# board.net
KiCad netlist of a schematic drawn in EAGLE
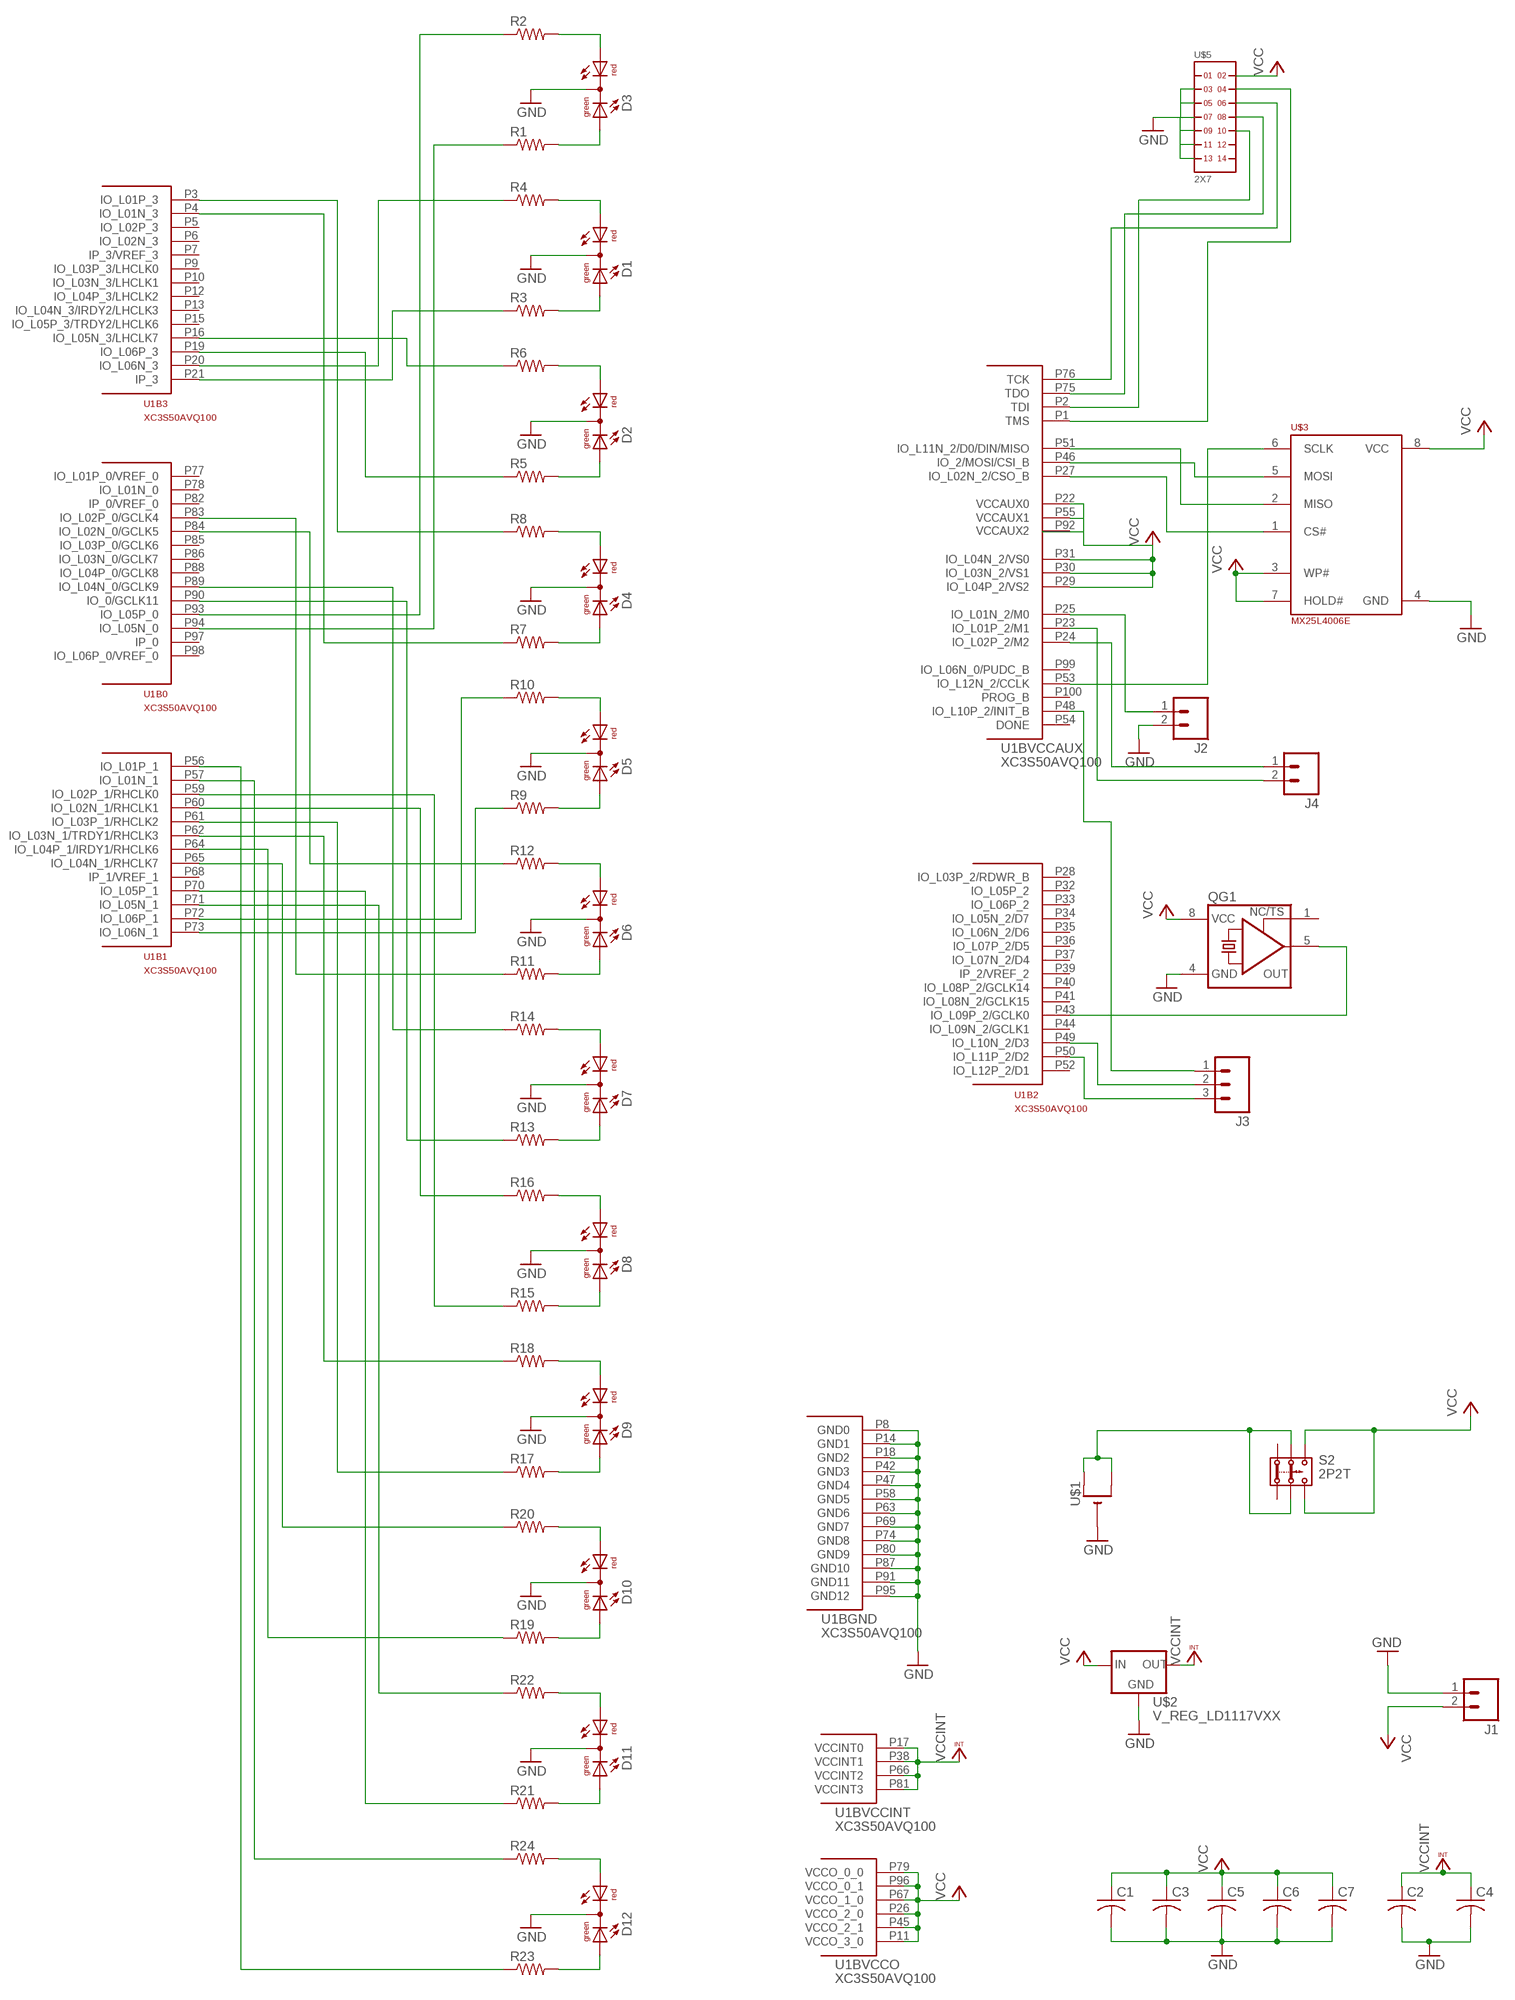
[diagram p0: schematic, sheet 1]

(export (version "E")
  (design (tool "Eeschema 10.0.6"))
  (components
    (comp (ref "C1")
      (value "C-USC0805")
      (footprint "eagle-import:C0805")
      (libsource (lib "eagle-import") (part "C-USC0805"))
    )
    (comp (ref "C2")
      (value "C-USC0805")
      (footprint "eagle-import:C0805")
      (libsource (lib "eagle-import") (part "C-USC0805"))
    )
    (comp (ref "C3")
      (value "C-USC0805")
      (footprint "eagle-import:C0805")
      (libsource (lib "eagle-import") (part "C-USC0805"))
    )
    (comp (ref "C4")
      (value "C-USC0805")
      (footprint "eagle-import:C0805")
      (libsource (lib "eagle-import") (part "C-USC0805"))
    )
    (comp (ref "C5")
      (value "C-USC0805")
      (footprint "eagle-import:C0805")
      (libsource (lib "eagle-import") (part "C-USC0805"))
    )
    (comp (ref "C6")
      (value "C-USC0805")
      (footprint "eagle-import:C0805")
      (libsource (lib "eagle-import") (part "C-USC0805"))
    )
    (comp (ref "C7")
      (value "C-USC0805")
      (footprint "eagle-import:C0805")
      (libsource (lib "eagle-import") (part "C-USC0805"))
    )
    (comp (ref "D1")
      (value "DUOLED5MM")
      (footprint "eagle-import:DUOLED5MM")
      (libsource (lib "eagle-import") (part "DUOLED5MM"))
    )
    (comp (ref "D2")
      (value "DUOLED5MM")
      (footprint "eagle-import:DUOLED5MM")
      (libsource (lib "eagle-import") (part "DUOLED5MM"))
    )
    (comp (ref "D3")
      (value "DUOLED5MM")
      (footprint "eagle-import:DUOLED5MM")
      (libsource (lib "eagle-import") (part "DUOLED5MM"))
    )
    (comp (ref "D4")
      (value "DUOLED5MM")
      (footprint "eagle-import:DUOLED5MM")
      (libsource (lib "eagle-import") (part "DUOLED5MM"))
    )
    (comp (ref "D5")
      (value "DUOLED5MM")
      (footprint "eagle-import:DUOLED5MM")
      (libsource (lib "eagle-import") (part "DUOLED5MM"))
    )
    (comp (ref "D6")
      (value "DUOLED5MM")
      (footprint "eagle-import:DUOLED5MM")
      (libsource (lib "eagle-import") (part "DUOLED5MM"))
    )
    (comp (ref "D7")
      (value "DUOLED5MM")
      (footprint "eagle-import:DUOLED5MM")
      (libsource (lib "eagle-import") (part "DUOLED5MM"))
    )
    (comp (ref "D8")
      (value "DUOLED5MM")
      (footprint "eagle-import:DUOLED5MM")
      (libsource (lib "eagle-import") (part "DUOLED5MM"))
    )
    (comp (ref "D9")
      (value "DUOLED5MM")
      (footprint "eagle-import:DUOLED5MM")
      (libsource (lib "eagle-import") (part "DUOLED5MM"))
    )
    (comp (ref "D10")
      (value "DUOLED5MM")
      (footprint "eagle-import:DUOLED5MM")
      (libsource (lib "eagle-import") (part "DUOLED5MM"))
    )
    (comp (ref "D11")
      (value "DUOLED5MM")
      (footprint "eagle-import:DUOLED5MM")
      (libsource (lib "eagle-import") (part "DUOLED5MM"))
    )
    (comp (ref "D12")
      (value "DUOLED5MM")
      (footprint "eagle-import:DUOLED5MM")
      (libsource (lib "eagle-import") (part "DUOLED5MM"))
    )
    (comp (ref "J1")
      (value "M02LOCK")
      (footprint "eagle-import:1X02_LOCK")
      (libsource (lib "eagle-import") (part "M02LOCK"))
    )
    (comp (ref "J2")
      (value "M02LOCK")
      (footprint "eagle-import:1X02_LOCK")
      (libsource (lib "eagle-import") (part "M02LOCK"))
    )
    (comp (ref "J3")
      (value "M03LOCK")
      (footprint "eagle-import:1X03_LOCK")
      (libsource (lib "eagle-import") (part "M03LOCK"))
    )
    (comp (ref "J4")
      (value "M02LOCK")
      (footprint "eagle-import:1X02_LOCK")
      (libsource (lib "eagle-import") (part "M02LOCK"))
    )
    (comp (ref "QG1")
      (value "XO-8")
      (footprint "eagle-import:DIL08S")
      (libsource (lib "eagle-import") (part "XO-8"))
    )
    (comp (ref "R1")
      (value "R-US_0204/7")
      (footprint "eagle-import:0204_7")
      (libsource (lib "eagle-import") (part "R-US_0204/7"))
    )
    (comp (ref "R2")
      (value "R-US_0204/7")
      (footprint "eagle-import:0204_7")
      (libsource (lib "eagle-import") (part "R-US_0204/7"))
    )
    (comp (ref "R3")
      (value "R-US_0204/7")
      (footprint "eagle-import:0204_7")
      (libsource (lib "eagle-import") (part "R-US_0204/7"))
    )
    (comp (ref "R4")
      (value "R-US_0204/7")
      (footprint "eagle-import:0204_7")
      (libsource (lib "eagle-import") (part "R-US_0204/7"))
    )
    (comp (ref "R5")
      (value "R-US_0204/7")
      (footprint "eagle-import:0204_7")
      (libsource (lib "eagle-import") (part "R-US_0204/7"))
    )
    (comp (ref "R6")
      (value "R-US_0204/7")
      (footprint "eagle-import:0204_7")
      (libsource (lib "eagle-import") (part "R-US_0204/7"))
    )
    (comp (ref "R7")
      (value "R-US_0204/7")
      (footprint "eagle-import:0204_7")
      (libsource (lib "eagle-import") (part "R-US_0204/7"))
    )
    (comp (ref "R8")
      (value "R-US_0204/7")
      (footprint "eagle-import:0204_7")
      (libsource (lib "eagle-import") (part "R-US_0204/7"))
    )
    (comp (ref "R9")
      (value "R-US_0204/7")
      (footprint "eagle-import:0204_7")
      (libsource (lib "eagle-import") (part "R-US_0204/7"))
    )
    (comp (ref "R10")
      (value "R-US_0204/7")
      (footprint "eagle-import:0204_7")
      (libsource (lib "eagle-import") (part "R-US_0204/7"))
    )
    (comp (ref "R11")
      (value "R-US_0204/7")
      (footprint "eagle-import:0204_7")
      (libsource (lib "eagle-import") (part "R-US_0204/7"))
    )
    (comp (ref "R12")
      (value "R-US_0204/7")
      (footprint "eagle-import:0204_7")
      (libsource (lib "eagle-import") (part "R-US_0204/7"))
    )
    (comp (ref "R13")
      (value "R-US_0204/7")
      (footprint "eagle-import:0204_7")
      (libsource (lib "eagle-import") (part "R-US_0204/7"))
    )
    (comp (ref "R14")
      (value "R-US_0204/7")
      (footprint "eagle-import:0204_7")
      (libsource (lib "eagle-import") (part "R-US_0204/7"))
    )
    (comp (ref "R15")
      (value "R-US_0204/7")
      (footprint "eagle-import:0204_7")
      (libsource (lib "eagle-import") (part "R-US_0204/7"))
    )
    (comp (ref "R16")
      (value "R-US_0204/7")
      (footprint "eagle-import:0204_7")
      (libsource (lib "eagle-import") (part "R-US_0204/7"))
    )
    (comp (ref "R17")
      (value "R-US_0204/7")
      (footprint "eagle-import:0204_7")
      (libsource (lib "eagle-import") (part "R-US_0204/7"))
    )
    (comp (ref "R18")
      (value "R-US_0204/7")
      (footprint "eagle-import:0204_7")
      (libsource (lib "eagle-import") (part "R-US_0204/7"))
    )
    (comp (ref "R19")
      (value "R-US_0204/7")
      (footprint "eagle-import:0204_7")
      (libsource (lib "eagle-import") (part "R-US_0204/7"))
    )
    (comp (ref "R20")
      (value "R-US_0204/7")
      (footprint "eagle-import:0204_7")
      (libsource (lib "eagle-import") (part "R-US_0204/7"))
    )
    (comp (ref "R21")
      (value "R-US_0204/7")
      (footprint "eagle-import:0204_7")
      (libsource (lib "eagle-import") (part "R-US_0204/7"))
    )
    (comp (ref "R22")
      (value "R-US_0204/7")
      (footprint "eagle-import:0204_7")
      (libsource (lib "eagle-import") (part "R-US_0204/7"))
    )
    (comp (ref "R23")
      (value "R-US_0204/7")
      (footprint "eagle-import:0204_7")
      (libsource (lib "eagle-import") (part "R-US_0204/7"))
    )
    (comp (ref "R24")
      (value "R-US_0204/7")
      (footprint "eagle-import:0204_7")
      (libsource (lib "eagle-import") (part "R-US_0204/7"))
    )
    (comp (ref "S2")
      (value "2P2T")
      (footprint "eagle-import:2P2T")
      (libsource (lib "eagle-import") (part "2P2T"))
    )
    (comp (ref "U$1")
      (value "CR2032THM")
      (footprint "eagle-import:CR2032-THRU")
      (libsource (lib "eagle-import") (part "CR2032THM"))
    )
    (comp (ref "U$2")
      (value "V_REG_LD1117VXX")
      (footprint "eagle-import:78XXL")
      (libsource (lib "eagle-import") (part "V_REG_LD1117VXX"))
    )
    (comp (ref "U$3")
      (value "MX25L4006E")
      (footprint "eagle-import:DIL08")
      (libsource (lib "eagle-import") (part "MX25L4006E"))
    )
    (comp (ref "U$5")
      (value "2X7")
      (footprint "eagle-import:2X7")
      (libsource (lib "eagle-import") (part "2X7"))
    )
    (comp (ref "U1")
      (value "XC3S50AVQ100")
      (footprint "eagle-import:VQ100")
      (libsource (lib "eagle-import") (part "XC3S50AVQ100"))
    )
  )
  (nets
    (net (code "1") (name "GND") (class "Default")
      (node (ref "C1") (pin "2") (pinfunction "2_2") (pintype "passive"))
      (node (ref "C2") (pin "2") (pinfunction "2_2") (pintype "passive"))
      (node (ref "C3") (pin "2") (pinfunction "2_2") (pintype "passive"))
      (node (ref "C4") (pin "2") (pinfunction "2_2") (pintype "passive"))
      (node (ref "C5") (pin "2") (pinfunction "2_2") (pintype "passive"))
      (node (ref "C6") (pin "2") (pinfunction "2_2") (pintype "passive"))
      (node (ref "C7") (pin "2") (pinfunction "2_2") (pintype "passive"))
      (node (ref "D1") (pin "K") (pinfunction "C_K") (pintype "passive"))
      (node (ref "D10") (pin "K") (pinfunction "C_K") (pintype "passive"))
      (node (ref "D11") (pin "K") (pinfunction "C_K") (pintype "passive"))
      (node (ref "D12") (pin "K") (pinfunction "C_K") (pintype "passive"))
      (node (ref "D2") (pin "K") (pinfunction "C_K") (pintype "passive"))
      (node (ref "D3") (pin "K") (pinfunction "C_K") (pintype "passive"))
      (node (ref "D4") (pin "K") (pinfunction "C_K") (pintype "passive"))
      (node (ref "D5") (pin "K") (pinfunction "C_K") (pintype "passive"))
      (node (ref "D6") (pin "K") (pinfunction "C_K") (pintype "passive"))
      (node (ref "D7") (pin "K") (pinfunction "C_K") (pintype "passive"))
      (node (ref "D8") (pin "K") (pinfunction "C_K") (pintype "passive"))
      (node (ref "D9") (pin "K") (pinfunction "C_K") (pintype "passive"))
      (node (ref "J1") (pin "1") (pinfunction "1_1") (pintype "passive"))
      (node (ref "J2") (pin "2") (pinfunction "2_2") (pintype "passive"))
      (node (ref "QG1") (pin "4") (pinfunction "GND_4") (pintype "power_in"))
      (node (ref "U$1") (pin "-") (pinfunction "-_-") (pintype "passive"))
      (node (ref "U$2") (pin "IN") (pinfunction "GND_IN") (pintype "input"))
      (node (ref "U$3") (pin "4") (pinfunction "GND_4") (pintype "bidirectional"))
      (node (ref "U$5") (pin "11") (pinfunction "11_11") (pintype "bidirectional"))
      (node (ref "U$5") (pin "13") (pinfunction "13_13") (pintype "bidirectional"))
      (node (ref "U$5") (pin "3") (pinfunction "3_3") (pintype "bidirectional"))
      (node (ref "U$5") (pin "5") (pinfunction "5_5") (pintype "bidirectional"))
      (node (ref "U$5") (pin "7") (pinfunction "7_7") (pintype "bidirectional"))
      (node (ref "U$5") (pin "9") (pinfunction "9_9") (pintype "bidirectional"))
      (node (ref "U1") (pin "P14") (pinfunction "GND1_P14") (pintype "passive"))
      (node (ref "U1") (pin "P18") (pinfunction "GND2_P18") (pintype "passive"))
      (node (ref "U1") (pin "P42") (pinfunction "GND3_P42") (pintype "passive"))
      (node (ref "U1") (pin "P47") (pinfunction "GND4_P47") (pintype "passive"))
      (node (ref "U1") (pin "P58") (pinfunction "GND5_P58") (pintype "passive"))
      (node (ref "U1") (pin "P63") (pinfunction "GND6_P63") (pintype "passive"))
      (node (ref "U1") (pin "P69") (pinfunction "GND7_P69") (pintype "passive"))
      (node (ref "U1") (pin "P74") (pinfunction "GND8_P74") (pintype "passive"))
      (node (ref "U1") (pin "P8") (pinfunction "GND0_P8") (pintype "passive"))
      (node (ref "U1") (pin "P80") (pinfunction "GND9_P80") (pintype "passive"))
      (node (ref "U1") (pin "P87") (pinfunction "GND10_P87") (pintype "passive"))
      (node (ref "U1") (pin "P91") (pinfunction "GND11_P91") (pintype "passive"))
      (node (ref "U1") (pin "P95") (pinfunction "GND12_P95") (pintype "passive"))
    )
    (net (code "2") (name "Net-(D1-PadAG)") (class "Default")
      (node (ref "D1") (pin "AG") (pinfunction "AG_AG") (pintype "passive"))
      (node (ref "R3") (pin "2") (pinfunction "2_2") (pintype "passive"))
    )
    (net (code "3") (name "Net-(D1-PadAR)") (class "Default")
      (node (ref "D1") (pin "AR") (pinfunction "AR_AR") (pintype "passive"))
      (node (ref "R4") (pin "2") (pinfunction "2_2") (pintype "passive"))
    )
    (net (code "4") (name "Net-(D2-PadAG)") (class "Default")
      (node (ref "D2") (pin "AG") (pinfunction "AG_AG") (pintype "passive"))
      (node (ref "R5") (pin "2") (pinfunction "2_2") (pintype "passive"))
    )
    (net (code "5") (name "Net-(D2-PadAR)") (class "Default")
      (node (ref "D2") (pin "AR") (pinfunction "AR_AR") (pintype "passive"))
      (node (ref "R6") (pin "2") (pinfunction "2_2") (pintype "passive"))
    )
    (net (code "6") (name "Net-(D3-PadAG)") (class "Default")
      (node (ref "D3") (pin "AG") (pinfunction "AG_AG") (pintype "passive"))
      (node (ref "R1") (pin "2") (pinfunction "2_2") (pintype "passive"))
    )
    (net (code "7") (name "Net-(D3-PadAR)") (class "Default")
      (node (ref "D3") (pin "AR") (pinfunction "AR_AR") (pintype "passive"))
      (node (ref "R2") (pin "2") (pinfunction "2_2") (pintype "passive"))
    )
    (net (code "8") (name "Net-(D4-PadAG)") (class "Default")
      (node (ref "D4") (pin "AG") (pinfunction "AG_AG") (pintype "passive"))
      (node (ref "R7") (pin "2") (pinfunction "2_2") (pintype "passive"))
    )
    (net (code "9") (name "Net-(D4-PadAR)") (class "Default")
      (node (ref "D4") (pin "AR") (pinfunction "AR_AR") (pintype "passive"))
      (node (ref "R8") (pin "2") (pinfunction "2_2") (pintype "passive"))
    )
    (net (code "10") (name "Net-(D5-PadAG)") (class "Default")
      (node (ref "D5") (pin "AG") (pinfunction "AG_AG") (pintype "passive"))
      (node (ref "R9") (pin "2") (pinfunction "2_2") (pintype "passive"))
    )
    (net (code "11") (name "Net-(D5-PadAR)") (class "Default")
      (node (ref "D5") (pin "AR") (pinfunction "AR_AR") (pintype "passive"))
      (node (ref "R10") (pin "2") (pinfunction "2_2") (pintype "passive"))
    )
    (net (code "12") (name "Net-(D6-PadAG)") (class "Default")
      (node (ref "D6") (pin "AG") (pinfunction "AG_AG") (pintype "passive"))
      (node (ref "R11") (pin "2") (pinfunction "2_2") (pintype "passive"))
    )
    (net (code "13") (name "Net-(D6-PadAR)") (class "Default")
      (node (ref "D6") (pin "AR") (pinfunction "AR_AR") (pintype "passive"))
      (node (ref "R12") (pin "2") (pinfunction "2_2") (pintype "passive"))
    )
    (net (code "14") (name "Net-(D7-PadAG)") (class "Default")
      (node (ref "D7") (pin "AG") (pinfunction "AG_AG") (pintype "passive"))
      (node (ref "R13") (pin "2") (pinfunction "2_2") (pintype "passive"))
    )
    (net (code "15") (name "Net-(D7-PadAR)") (class "Default")
      (node (ref "D7") (pin "AR") (pinfunction "AR_AR") (pintype "passive"))
      (node (ref "R14") (pin "2") (pinfunction "2_2") (pintype "passive"))
    )
    (net (code "16") (name "Net-(D8-PadAG)") (class "Default")
      (node (ref "D8") (pin "AG") (pinfunction "AG_AG") (pintype "passive"))
      (node (ref "R15") (pin "2") (pinfunction "2_2") (pintype "passive"))
    )
    (net (code "17") (name "Net-(D8-PadAR)") (class "Default")
      (node (ref "D8") (pin "AR") (pinfunction "AR_AR") (pintype "passive"))
      (node (ref "R16") (pin "2") (pinfunction "2_2") (pintype "passive"))
    )
    (net (code "18") (name "Net-(D9-PadAG)") (class "Default")
      (node (ref "D9") (pin "AG") (pinfunction "AG_AG") (pintype "passive"))
      (node (ref "R17") (pin "2") (pinfunction "2_2") (pintype "passive"))
    )
    (net (code "19") (name "Net-(D9-PadAR)") (class "Default")
      (node (ref "D9") (pin "AR") (pinfunction "AR_AR") (pintype "passive"))
      (node (ref "R18") (pin "2") (pinfunction "2_2") (pintype "passive"))
    )
    (net (code "20") (name "Net-(D10-PadAG)") (class "Default")
      (node (ref "D10") (pin "AG") (pinfunction "AG_AG") (pintype "passive"))
      (node (ref "R19") (pin "2") (pinfunction "2_2") (pintype "passive"))
    )
    (net (code "21") (name "Net-(D10-PadAR)") (class "Default")
      (node (ref "D10") (pin "AR") (pinfunction "AR_AR") (pintype "passive"))
      (node (ref "R20") (pin "2") (pinfunction "2_2") (pintype "passive"))
    )
    (net (code "22") (name "Net-(D11-PadAG)") (class "Default")
      (node (ref "D11") (pin "AG") (pinfunction "AG_AG") (pintype "passive"))
      (node (ref "R21") (pin "2") (pinfunction "2_2") (pintype "passive"))
    )
    (net (code "23") (name "Net-(D11-PadAR)") (class "Default")
      (node (ref "D11") (pin "AR") (pinfunction "AR_AR") (pintype "passive"))
      (node (ref "R22") (pin "2") (pinfunction "2_2") (pintype "passive"))
    )
    (net (code "24") (name "Net-(D12-PadAG)") (class "Default")
      (node (ref "D12") (pin "AG") (pinfunction "AG_AG") (pintype "passive"))
      (node (ref "R23") (pin "2") (pinfunction "2_2") (pintype "passive"))
    )
    (net (code "25") (name "Net-(D12-PadAR)") (class "Default")
      (node (ref "D12") (pin "AR") (pinfunction "AR_AR") (pintype "passive"))
      (node (ref "R24") (pin "2") (pinfunction "2_2") (pintype "passive"))
    )
    (net (code "26") (name "Net-(QG1-OUT)") (class "Default")
      (node (ref "QG1") (pin "5") (pinfunction "OUT_5") (pintype "output"))
      (node (ref "U1") (pin "P43") (pinfunction "IO_L09P_2/GCLK0_P43") (pintype "bidirectional"))
    )
    (net (code "27") (name "Net-(U$1-+)") (class "Default")
      (node (ref "S2") (pin "2.1") (pinfunction "2.1_2.1") (pintype "passive"))
      (node (ref "S2") (pin "2.2") (pinfunction "2.2_2.2") (pintype "passive"))
      (node (ref "U$1") (pin "+1") (pinfunction "+_+1") (pintype "passive"))
      (node (ref "U$1") (pin "+2") (pinfunction "+1_+2") (pintype "passive"))
    )
    (net (code "28") (name "Net-(U$3-CS#)") (class "Default")
      (node (ref "U$3") (pin "1") (pinfunction "CS#_1") (pintype "bidirectional"))
      (node (ref "U1") (pin "P27") (pinfunction "IO_L02N_2/CSO_B_P27") (pintype "bidirectional"))
    )
    (net (code "29") (name "Net-(U$3-MISO)") (class "Default")
      (node (ref "U$3") (pin "2") (pinfunction "MISO_2") (pintype "bidirectional"))
      (node (ref "U1") (pin "P51") (pinfunction "IO_L11N_2/D0/DIN/MISO_P51") (pintype "bidirectional"))
    )
    (net (code "30") (name "Net-(U$3-MOSI)") (class "Default")
      (node (ref "U$3") (pin "5") (pinfunction "MOSI_5") (pintype "bidirectional"))
      (node (ref "U1") (pin "P46") (pinfunction "IO_2/MOSI/CSI_B_P46") (pintype "bidirectional"))
    )
    (net (code "31") (name "Net-(U$3-SCLK)") (class "Default")
      (node (ref "U$3") (pin "6") (pinfunction "SCLK_6") (pintype "bidirectional"))
      (node (ref "U1") (pin "P53") (pinfunction "IO_L12N_2/CCLK_P53") (pintype "bidirectional"))
    )
    (net (code "32") (name "Net-(U1A-IO_0{slash}GCLK11)") (class "Default")
      (node (ref "R13") (pin "1") (pinfunction "1_1") (pintype "passive"))
      (node (ref "U1") (pin "P90") (pinfunction "IO_0/GCLK11_P90") (pintype "bidirectional"))
    )
    (net (code "33") (name "Net-(U1A-IO_L02N_0{slash}GCLK5)") (class "Default")
      (node (ref "R12") (pin "1") (pinfunction "1_1") (pintype "passive"))
      (node (ref "U1") (pin "P84") (pinfunction "IO_L02N_0/GCLK5_P84") (pintype "bidirectional"))
    )
    (net (code "34") (name "Net-(U1A-IO_L02P_0{slash}GCLK4)") (class "Default")
      (node (ref "R11") (pin "1") (pinfunction "1_1") (pintype "passive"))
      (node (ref "U1") (pin "P83") (pinfunction "IO_L02P_0/GCLK4_P83") (pintype "bidirectional"))
    )
    (net (code "35") (name "Net-(U1A-IO_L04N_0{slash}GCLK9)") (class "Default")
      (node (ref "R14") (pin "1") (pinfunction "1_1") (pintype "passive"))
      (node (ref "U1") (pin "P89") (pinfunction "IO_L04N_0/GCLK9_P89") (pintype "bidirectional"))
    )
    (net (code "36") (name "Net-(U1A-IO_L05N_0)") (class "Default")
      (node (ref "R1") (pin "1") (pinfunction "1_1") (pintype "passive"))
      (node (ref "U1") (pin "P94") (pinfunction "IO_L05N_0_P94") (pintype "bidirectional"))
    )
    (net (code "37") (name "Net-(U1A-IO_L05P_0)") (class "Default")
      (node (ref "R2") (pin "1") (pinfunction "1_1") (pintype "passive"))
      (node (ref "U1") (pin "P93") (pinfunction "IO_L05P_0_P93") (pintype "bidirectional"))
    )
    (net (code "38") (name "Net-(U1B-IO_L01N_1)") (class "Default")
      (node (ref "R24") (pin "1") (pinfunction "1_1") (pintype "passive"))
      (node (ref "U1") (pin "P57") (pinfunction "IO_L01N_1_P57") (pintype "bidirectional"))
    )
    (net (code "39") (name "Net-(U1B-IO_L01P_1)") (class "Default")
      (node (ref "R23") (pin "1") (pinfunction "1_1") (pintype "passive"))
      (node (ref "U1") (pin "P56") (pinfunction "IO_L01P_1_P56") (pintype "bidirectional"))
    )
    (net (code "40") (name "Net-(U1B-IO_L02N_1{slash}RHCLK1)") (class "Default")
      (node (ref "R16") (pin "1") (pinfunction "1_1") (pintype "passive"))
      (node (ref "U1") (pin "P60") (pinfunction "IO_L02N_1/RHCLK1_P60") (pintype "bidirectional"))
    )
    (net (code "41") (name "Net-(U1B-IO_L02P_1{slash}RHCLK0)") (class "Default")
      (node (ref "R15") (pin "1") (pinfunction "1_1") (pintype "passive"))
      (node (ref "U1") (pin "P59") (pinfunction "IO_L02P_1/RHCLK0_P59") (pintype "bidirectional"))
    )
    (net (code "42") (name "Net-(U1B-IO_L03N_1{slash}TRDY1{slash}RHCLK3)") (class "Default")
      (node (ref "R18") (pin "1") (pinfunction "1_1") (pintype "passive"))
      (node (ref "U1") (pin "P62") (pinfunction "IO_L03N_1/TRDY1/RHCLK3_P62") (pintype "bidirectional"))
    )
    (net (code "43") (name "Net-(U1B-IO_L03P_1{slash}RHCLK2)") (class "Default")
      (node (ref "R17") (pin "1") (pinfunction "1_1") (pintype "passive"))
      (node (ref "U1") (pin "P61") (pinfunction "IO_L03P_1/RHCLK2_P61") (pintype "bidirectional"))
    )
    (net (code "44") (name "Net-(U1B-IO_L04N_1{slash}RHCLK7)") (class "Default")
      (node (ref "R20") (pin "1") (pinfunction "1_1") (pintype "passive"))
      (node (ref "U1") (pin "P65") (pinfunction "IO_L04N_1/RHCLK7_P65") (pintype "bidirectional"))
    )
    (net (code "45") (name "Net-(U1B-IO_L04P_1{slash}IRDY1{slash}RHCLK6)") (class "Default")
      (node (ref "R19") (pin "1") (pinfunction "1_1") (pintype "passive"))
      (node (ref "U1") (pin "P64") (pinfunction "IO_L04P_1/IRDY1/RHCLK6_P64") (pintype "bidirectional"))
    )
    (net (code "46") (name "Net-(U1B-IO_L05N_1)") (class "Default")
      (node (ref "R22") (pin "1") (pinfunction "1_1") (pintype "passive"))
      (node (ref "U1") (pin "P71") (pinfunction "IO_L05N_1_P71") (pintype "bidirectional"))
    )
    (net (code "47") (name "Net-(U1B-IO_L05P_1)") (class "Default")
      (node (ref "R21") (pin "1") (pinfunction "1_1") (pintype "passive"))
      (node (ref "U1") (pin "P70") (pinfunction "IO_L05P_1_P70") (pintype "bidirectional"))
    )
    (net (code "48") (name "Net-(U1B-IO_L06N_1)") (class "Default")
      (node (ref "R9") (pin "1") (pinfunction "1_1") (pintype "passive"))
      (node (ref "U1") (pin "P73") (pinfunction "IO_L06N_1_P73") (pintype "bidirectional"))
    )
    (net (code "49") (name "Net-(U1B-IO_L06P_1)") (class "Default")
      (node (ref "R10") (pin "1") (pinfunction "1_1") (pintype "passive"))
      (node (ref "U1") (pin "P72") (pinfunction "IO_L06P_1_P72") (pintype "bidirectional"))
    )
    (net (code "50") (name "Net-(U1C-IO_L10N_2{slash}D3)") (class "Default")
      (node (ref "J3") (pin "2") (pinfunction "2_2") (pintype "passive"))
      (node (ref "U1") (pin "P49") (pinfunction "IO_L10N_2/D3_P49") (pintype "bidirectional"))
    )
    (net (code "51") (name "Net-(U1C-IO_L11P_2{slash}D2)") (class "Default")
      (node (ref "J3") (pin "3") (pinfunction "3_3") (pintype "passive"))
      (node (ref "U1") (pin "P50") (pinfunction "IO_L11P_2/D2_P50") (pintype "bidirectional"))
    )
    (net (code "52") (name "Net-(U1D-IO_L01N_3)") (class "Default")
      (node (ref "R7") (pin "1") (pinfunction "1_1") (pintype "passive"))
      (node (ref "U1") (pin "P4") (pinfunction "IO_L01N_3_P4") (pintype "bidirectional"))
    )
    (net (code "53") (name "Net-(U1D-IO_L01P_3)") (class "Default")
      (node (ref "R8") (pin "1") (pinfunction "1_1") (pintype "passive"))
      (node (ref "U1") (pin "P3") (pinfunction "IO_L01P_3_P3") (pintype "bidirectional"))
    )
    (net (code "54") (name "Net-(U1D-IO_L05N_3{slash}LHCLK7)") (class "Default")
      (node (ref "R6") (pin "1") (pinfunction "1_1") (pintype "passive"))
      (node (ref "U1") (pin "P16") (pinfunction "IO_L05N_3/LHCLK7_P16") (pintype "bidirectional"))
    )
    (net (code "55") (name "Net-(U1D-IO_L06N_3)") (class "Default")
      (node (ref "R4") (pin "1") (pinfunction "1_1") (pintype "passive"))
      (node (ref "U1") (pin "P20") (pinfunction "IO_L06N_3_P20") (pintype "bidirectional"))
    )
    (net (code "56") (name "Net-(U1D-IO_L06P_3)") (class "Default")
      (node (ref "R5") (pin "1") (pinfunction "1_1") (pintype "passive"))
      (node (ref "U1") (pin "P19") (pinfunction "IO_L06P_3_P19") (pintype "bidirectional"))
    )
    (net (code "57") (name "Net-(U1D-IP_3)") (class "Default")
      (node (ref "R3") (pin "1") (pinfunction "1_1") (pintype "passive"))
      (node (ref "U1") (pin "P21") (pinfunction "IP_3_P21") (pintype "bidirectional"))
    )
    (net (code "58") (name "Net-(U1F-IO_L01N_2{slash}M0)") (class "Default")
      (node (ref "J2") (pin "1") (pinfunction "1_1") (pintype "passive"))
      (node (ref "U1") (pin "P25") (pinfunction "IO_L01N_2/M0_P25") (pintype "bidirectional"))
    )
    (net (code "59") (name "Net-(U1F-IO_L01P_2{slash}M1)") (class "Default")
      (node (ref "J4") (pin "2") (pinfunction "2_2") (pintype "passive"))
      (node (ref "U1") (pin "P23") (pinfunction "IO_L01P_2/M1_P23") (pintype "bidirectional"))
    )
    (net (code "60") (name "Net-(U1F-IO_L02P_2{slash}M2)") (class "Default")
      (node (ref "J4") (pin "1") (pinfunction "1_1") (pintype "passive"))
      (node (ref "U1") (pin "P24") (pinfunction "IO_L02P_2/M2_P24") (pintype "bidirectional"))
    )
    (net (code "61") (name "Net-(U1F-IO_L10P_2{slash}INIT_B)") (class "Default")
      (node (ref "J3") (pin "1") (pinfunction "1_1") (pintype "passive"))
      (node (ref "U1") (pin "P48") (pinfunction "IO_L10P_2/INIT_B_P48") (pintype "bidirectional"))
    )
    (net (code "62") (name "Net-(U1F-TCK)") (class "Default")
      (node (ref "U$5") (pin "6") (pinfunction "6_6") (pintype "bidirectional"))
      (node (ref "U1") (pin "P76") (pinfunction "TCK_P76") (pintype "bidirectional"))
    )
    (net (code "63") (name "Net-(U1F-TDI)") (class "Default")
      (node (ref "U$5") (pin "10") (pinfunction "10_10") (pintype "bidirectional"))
      (node (ref "U1") (pin "P2") (pinfunction "TDI_P2") (pintype "bidirectional"))
    )
    (net (code "64") (name "Net-(U1F-TDO)") (class "Default")
      (node (ref "U$5") (pin "8") (pinfunction "8_8") (pintype "bidirectional"))
      (node (ref "U1") (pin "P75") (pinfunction "TDO_P75") (pintype "bidirectional"))
    )
    (net (code "65") (name "Net-(U1F-TMS)") (class "Default")
      (node (ref "U$5") (pin "4") (pinfunction "4_4") (pintype "bidirectional"))
      (node (ref "U1") (pin "P1") (pinfunction "TMS_P1") (pintype "bidirectional"))
    )
    (net (code "66") (name "VCC") (class "Default")
      (node (ref "C1") (pin "1") (pinfunction "1_1") (pintype "passive"))
      (node (ref "C3") (pin "1") (pinfunction "1_1") (pintype "passive"))
      (node (ref "C5") (pin "1") (pinfunction "1_1") (pintype "passive"))
      (node (ref "C6") (pin "1") (pinfunction "1_1") (pintype "passive"))
      (node (ref "C7") (pin "1") (pinfunction "1_1") (pintype "passive"))
      (node (ref "J1") (pin "2") (pinfunction "2_2") (pintype "passive"))
      (node (ref "QG1") (pin "8") (pinfunction "VCC_8") (pintype "power_in"))
      (node (ref "S2") (pin "3.1") (pinfunction "3.1_3.1") (pintype "passive"))
      (node (ref "S2") (pin "3.2") (pinfunction "3.2_3.2") (pintype "passive"))
      (node (ref "U$2") (pin "OUT") (pinfunction "IN_OUT") (pintype "input"))
      (node (ref "U$3") (pin "3") (pinfunction "WP#_3") (pintype "bidirectional"))
      (node (ref "U$3") (pin "7") (pinfunction "HOLD#_7") (pintype "bidirectional"))
      (node (ref "U$3") (pin "8") (pinfunction "VCC_8") (pintype "bidirectional"))
      (node (ref "U$5") (pin "2") (pinfunction "2_2") (pintype "bidirectional"))
      (node (ref "U1") (pin "P11") (pinfunction "VCCO_3_0_P11") (pintype "bidirectional"))
      (node (ref "U1") (pin "P22") (pinfunction "VCCAUX0_P22") (pintype "passive"))
      (node (ref "U1") (pin "P26") (pinfunction "VCCO_2_0_P26") (pintype "passive"))
      (node (ref "U1") (pin "P29") (pinfunction "IO_L04P_2/VS2_P29") (pintype "bidirectional"))
      (node (ref "U1") (pin "P30") (pinfunction "IO_L03N_2/VS1_P30") (pintype "bidirectional"))
      (node (ref "U1") (pin "P31") (pinfunction "IO_L04N_2/VS0_P31") (pintype "bidirectional"))
      (node (ref "U1") (pin "P45") (pinfunction "VCCO_2_1_P45") (pintype "bidirectional"))
      (node (ref "U1") (pin "P55") (pinfunction "VCCAUX1_P55") (pintype "passive"))
      (node (ref "U1") (pin "P67") (pinfunction "VCCO_1_0_P67") (pintype "passive"))
      (node (ref "U1") (pin "P79") (pinfunction "VCCO_0_0_P79") (pintype "passive"))
      (node (ref "U1") (pin "P96") (pinfunction "VCCO_0_1_P96") (pintype "passive"))
    )
    (net (code "67") (name "VCCINT") (class "Default")
      (node (ref "C2") (pin "1") (pinfunction "1_1") (pintype "passive"))
      (node (ref "C4") (pin "1") (pinfunction "1_1") (pintype "passive"))
      (node (ref "U$2") (pin "GND") (pinfunction "OUT_GND") (pintype "passive"))
      (node (ref "U1") (pin "P17") (pinfunction "VCCINT0_P17") (pintype "passive"))
      (node (ref "U1") (pin "P38") (pinfunction "VCCINT1_P38") (pintype "passive"))
      (node (ref "U1") (pin "P66") (pinfunction "VCCINT2_P66") (pintype "passive"))
      (node (ref "U1") (pin "P81") (pinfunction "VCCINT3_P81") (pintype "passive"))
    )
    (net (code "68") (name "unconnected-(QG1-TS-Pad1)") (class "Default")
      (node (ref "QG1") (pin "1") (pinfunction "TS_1") (pintype "passive"))
    )
    (net (code "69") (name "unconnected-(S2-Pad1.1)") (class "Default")
      (node (ref "S2") (pin "1.1") (pinfunction "1.1_1.1") (pintype "passive"))
    )
    (net (code "70") (name "unconnected-(S2-Pad1.2)") (class "Default")
      (node (ref "S2") (pin "1.2") (pinfunction "1.2_1.2") (pintype "passive"))
    )
    (net (code "71") (name "unconnected-(U$5-Pad1)") (class "Default")
      (node (ref "U$5") (pin "1") (pinfunction "1_1") (pintype "bidirectional"))
    )
    (net (code "72") (name "unconnected-(U$5-Pad12)") (class "Default")
      (node (ref "U$5") (pin "12") (pinfunction "12_12") (pintype "bidirectional"))
    )
    (net (code "73") (name "unconnected-(U$5-Pad14)") (class "Default")
      (node (ref "U$5") (pin "14") (pinfunction "14_14") (pintype "bidirectional"))
    )
    (net (code "74") (name "unconnected-(U1A-IO_L01N_0-PadP78)") (class "Default")
      (node (ref "U1") (pin "P78") (pinfunction "IO_L01N_0_P78") (pintype "bidirectional"))
    )
    (net (code "75") (name "unconnected-(U1A-IO_L01P_0{slash}VREF_0-PadP77)") (class "Default")
      (node (ref "U1") (pin "P77") (pinfunction "IO_L01P_0/VREF_0_P77") (pintype "bidirectional"))
    )
    (net (code "76") (name "unconnected-(U1A-IO_L03N_0{slash}GCLK7-PadP86)") (class "Default")
      (node (ref "U1") (pin "P86") (pinfunction "IO_L03N_0/GCLK7_P86") (pintype "bidirectional"))
    )
    (net (code "77") (name "unconnected-(U1A-IO_L03P_0{slash}GCLK6-PadP85)") (class "Default")
      (node (ref "U1") (pin "P85") (pinfunction "IO_L03P_0/GCLK6_P85") (pintype "bidirectional"))
    )
    (net (code "78") (name "unconnected-(U1A-IO_L04P_0{slash}GCLK8-PadP88)") (class "Default")
      (node (ref "U1") (pin "P88") (pinfunction "IO_L04P_0/GCLK8_P88") (pintype "bidirectional"))
    )
    (net (code "79") (name "unconnected-(U1A-IO_L06P_0{slash}VREF_0-PadP98)") (class "Default")
      (node (ref "U1") (pin "P98") (pinfunction "IO_L06P_0/VREF_0_P98") (pintype "bidirectional"))
    )
    (net (code "80") (name "unconnected-(U1A-IP_0-PadP97)") (class "Default")
      (node (ref "U1") (pin "P97") (pinfunction "IP_0_P97") (pintype "bidirectional"))
    )
    (net (code "81") (name "unconnected-(U1A-IP_0{slash}VREF_0-PadP82)") (class "Default")
      (node (ref "U1") (pin "P82") (pinfunction "IP_0/VREF_0_P82") (pintype "bidirectional"))
    )
    (net (code "82") (name "unconnected-(U1B-IP_1{slash}VREF_1-PadP68)") (class "Default")
      (node (ref "U1") (pin "P68") (pinfunction "IP_1/VREF_1_P68") (pintype "bidirectional"))
    )
    (net (code "83") (name "unconnected-(U1C-IO_L03P_2{slash}RDWR_B-PadP28)") (class "Default")
      (node (ref "U1") (pin "P28") (pinfunction "IO_L03P_2/RDWR_B_P28") (pintype "bidirectional"))
    )
    (net (code "84") (name "unconnected-(U1C-IO_L05N_2{slash}D7-PadP34)") (class "Default")
      (node (ref "U1") (pin "P34") (pinfunction "IO_L05N_2/D7_P34") (pintype "bidirectional"))
    )
    (net (code "85") (name "unconnected-(U1C-IO_L05P_2-PadP32)") (class "Default")
      (node (ref "U1") (pin "P32") (pinfunction "IO_L05P_2_P32") (pintype "bidirectional"))
    )
    (net (code "86") (name "unconnected-(U1C-IO_L06N_2{slash}D6-PadP35)") (class "Default")
      (node (ref "U1") (pin "P35") (pinfunction "IO_L06N_2/D6_P35") (pintype "bidirectional"))
    )
    (net (code "87") (name "unconnected-(U1C-IO_L06P_2-PadP33)") (class "Default")
      (node (ref "U1") (pin "P33") (pinfunction "IO_L06P_2_P33") (pintype "bidirectional"))
    )
    (net (code "88") (name "unconnected-(U1C-IO_L07N_2{slash}D4-PadP37)") (class "Default")
      (node (ref "U1") (pin "P37") (pinfunction "IO_L07N_2/D4_P37") (pintype "bidirectional"))
    )
    (net (code "89") (name "unconnected-(U1C-IO_L07P_2{slash}D5-PadP36)") (class "Default")
      (node (ref "U1") (pin "P36") (pinfunction "IO_L07P_2/D5_P36") (pintype "bidirectional"))
    )
    (net (code "90") (name "unconnected-(U1C-IO_L08N_2{slash}GCLK15-PadP41)") (class "Default")
      (node (ref "U1") (pin "P41") (pinfunction "IO_L08N_2/GCLK15_P41") (pintype "bidirectional"))
    )
    (net (code "91") (name "unconnected-(U1C-IO_L08P_2{slash}GCLK14-PadP40)") (class "Default")
      (node (ref "U1") (pin "P40") (pinfunction "IO_L08P_2/GCLK14_P40") (pintype "bidirectional"))
    )
    (net (code "92") (name "unconnected-(U1C-IO_L09N_2{slash}GCLK1-PadP44)") (class "Default")
      (node (ref "U1") (pin "P44") (pinfunction "IO_L09N_2/GCLK1_P44") (pintype "bidirectional"))
    )
    (net (code "93") (name "unconnected-(U1C-IO_L12P_2{slash}D1-PadP52)") (class "Default")
      (node (ref "U1") (pin "P52") (pinfunction "IO_L12P_2/D1_P52") (pintype "bidirectional"))
    )
    (net (code "94") (name "unconnected-(U1C-IP_2{slash}VREF_2-PadP39)") (class "Default")
      (node (ref "U1") (pin "P39") (pinfunction "IP_2/VREF_2_P39") (pintype "bidirectional"))
    )
    (net (code "95") (name "unconnected-(U1D-IO_L02N_3-PadP6)") (class "Default")
      (node (ref "U1") (pin "P6") (pinfunction "IO_L02N_3_P6") (pintype "bidirectional"))
    )
    (net (code "96") (name "unconnected-(U1D-IO_L02P_3-PadP5)") (class "Default")
      (node (ref "U1") (pin "P5") (pinfunction "IO_L02P_3_P5") (pintype "bidirectional"))
    )
    (net (code "97") (name "unconnected-(U1D-IO_L03N_3{slash}LHCLK1-PadP10)") (class "Default")
      (node (ref "U1") (pin "P10") (pinfunction "IO_L03N_3/LHCLK1_P10") (pintype "bidirectional"))
    )
    (net (code "98") (name "unconnected-(U1D-IO_L03P_3{slash}LHCLK0-PadP9)") (class "Default")
      (node (ref "U1") (pin "P9") (pinfunction "IO_L03P_3/LHCLK0_P9") (pintype "bidirectional"))
    )
    (net (code "99") (name "unconnected-(U1D-IO_L04N_3{slash}IRDY2{slash}LHCLK3-PadP13)") (class "Default")
      (node (ref "U1") (pin "P13") (pinfunction "IO_L04N_3/IRDY2/LHCLK3_P13") (pintype "bidirectional"))
    )
    (net (code "100") (name "unconnected-(U1D-IO_L04P_3{slash}LHCLK2-PadP12)") (class "Default")
      (node (ref "U1") (pin "P12") (pinfunction "IO_L04P_3/LHCLK2_P12") (pintype "bidirectional"))
    )
    (net (code "101") (name "unconnected-(U1D-IO_L05P_3{slash}TRDY2{slash}LHCLK6-PadP15)") (class "Default")
      (node (ref "U1") (pin "P15") (pinfunction "IO_L05P_3/TRDY2/LHCLK6_P15") (pintype "bidirectional"))
    )
    (net (code "102") (name "unconnected-(U1D-IP_3{slash}VREF_3-PadP7)") (class "Default")
      (node (ref "U1") (pin "P7") (pinfunction "IP_3/VREF_3_P7") (pintype "bidirectional"))
    )
    (net (code "103") (name "unconnected-(U1F-DONE-PadP54)") (class "Default")
      (node (ref "U1") (pin "P54") (pinfunction "DONE_P54") (pintype "bidirectional"))
    )
    (net (code "104") (name "unconnected-(U1F-IO_L06N_0{slash}PUDC_B-PadP99)") (class "Default")
      (node (ref "U1") (pin "P99") (pinfunction "IO_L06N_0/PUDC_B_P99") (pintype "bidirectional"))
    )
    (net (code "105") (name "unconnected-(U1F-PROG_B-PadP100)") (class "Default")
      (node (ref "U1") (pin "P100") (pinfunction "PROG_B_P100") (pintype "bidirectional"))
    )
    (net (code "106") (name "unconnected-(U1F-VCCAUX2-PadP92)") (class "Default")
      (node (ref "U1") (pin "P92") (pinfunction "VCCAUX2_P92") (pintype "passive"))
    )
  )
)
